# section2.net
KiCad netlist of a schematic drawn in EasyEDA
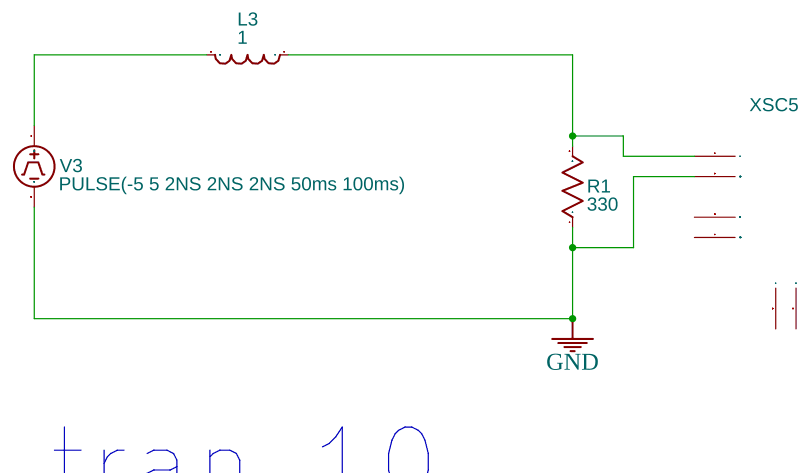
[diagram p0: schematic sheet]

(export (version "E")
  (design (tool "Eeschema 10.0.6"))
  (components
    (comp (ref "L3") (value "1") (libsource (lib "") (part "Inductor")))
    (comp (ref "R1") (value "330") (libsource (lib "") (part "Resistor_US")))
    (comp (ref "V3") (value "PULSE(-5 5 2NS 2NS 2NS 50ms 100ms)") (libsource (lib "") (part "VPULSE")))
    (comp (ref "XSC5") (value "Oscilloscope") (libsource (lib "") (part "OSCILLOSCOPE")))
  )
  (nets
    (net (code "1") (name "GND") (class "Default")
      (node (ref "R1") (pin "1") (pinfunction "1_1") (pintype "unspecified"))
      (node (ref "V3") (pin "2") (pinfunction "2_2") (pintype "unspecified"))
      (node (ref "XSC5") (pin "2") (pinfunction "GND1_2") (pintype "unspecified"))
    )
    (net (code "2") (name "Net-(L3-Pad2)") (class "Default")
      (node (ref "L3") (pin "2") (pinfunction "2_2") (pintype "unspecified"))
      (node (ref "V3") (pin "1") (pinfunction "1_1") (pintype "unspecified"))
    )
    (net (code "3") (name "Net-(XSC5-A)") (class "Default")
      (node (ref "L3") (pin "1") (pinfunction "1_1") (pintype "unspecified"))
      (node (ref "R1") (pin "2") (pinfunction "2_2") (pintype "unspecified"))
      (node (ref "XSC5") (pin "1") (pinfunction "A_1") (pintype "unspecified"))
    )
    (net (code "4") (name "unconnected-(XSC5-B-Pad3)") (class "Default")
      (node (ref "XSC5") (pin "3") (pinfunction "B_3") (pintype "unspecified"))
    )
    (net (code "5") (name "unconnected-(XSC5-GND2-Pad4)") (class "Default")
      (node (ref "XSC5") (pin "4") (pinfunction "GND2_4") (pintype "unspecified"))
    )
    (net (code "6") (name "unconnected-(XSC5-T+-Pad5)") (class "Default")
      (node (ref "XSC5") (pin "5") (pinfunction "T+_5") (pintype "unspecified"))
    )
    (net (code "7") (name "unconnected-(XSC5-T--Pad6)") (class "Default")
      (node (ref "XSC5") (pin "6") (pinfunction "T-_6") (pintype "unspecified"))
    )
  )
)
